# WaterCirculation.net
KiCad netlist of a schematic drawn in EAGLE
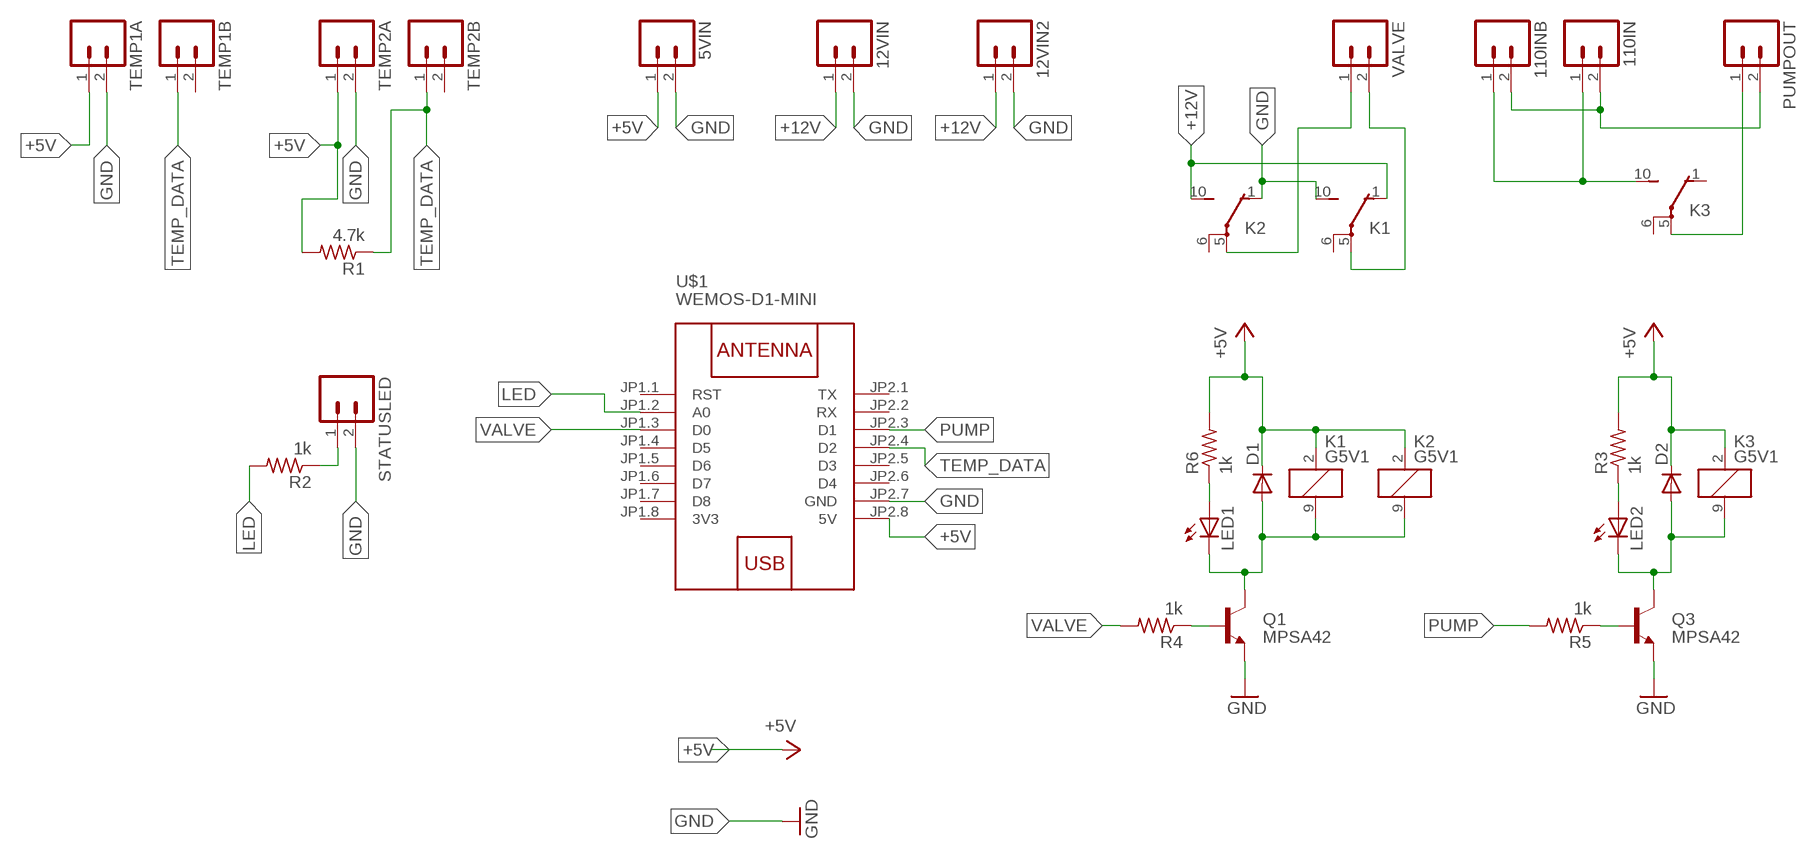
[diagram p0: schematic, sheet 1]

(export (version "E")
  (design (tool "Eeschema 10.0.6"))
  (components
    (comp (ref "5VIN")
      (value "M023.5MM")
      (footprint "eagle-import:SCREWTERMINAL-3.5MM-2")
      (libsource (lib "eagle-import") (part "M023.5MM"))
    )
    (comp (ref "12VIN")
      (value "M023.5MM")
      (footprint "eagle-import:SCREWTERMINAL-3.5MM-2")
      (libsource (lib "eagle-import") (part "M023.5MM"))
    )
    (comp (ref "12VIN2")
      (value "M023.5MM")
      (footprint "eagle-import:SCREWTERMINAL-3.5MM-2")
      (libsource (lib "eagle-import") (part "M023.5MM"))
    )
    (comp (ref "110IN")
      (value "M023.5MM")
      (footprint "eagle-import:SCREWTERMINAL-3.5MM-2")
      (libsource (lib "eagle-import") (part "M023.5MM"))
    )
    (comp (ref "110INB")
      (value "M023.5MM")
      (footprint "eagle-import:SCREWTERMINAL-3.5MM-2")
      (libsource (lib "eagle-import") (part "M023.5MM"))
    )
    (comp (ref "D1")
      (value "DIODE-SOD123")
      (footprint "eagle-import:SOD123")
      (libsource (lib "eagle-import") (part "DIODE-SOD123"))
    )
    (comp (ref "D2")
      (value "DIODE-SOD123")
      (footprint "eagle-import:SOD123")
      (libsource (lib "eagle-import") (part "DIODE-SOD123"))
    )
    (comp (ref "K1")
      (value "G5V1")
      (footprint "eagle-import:G5V1")
      (libsource (lib "eagle-import") (part "G5V1"))
    )
    (comp (ref "K2")
      (value "G5V1")
      (footprint "eagle-import:G5V1")
      (libsource (lib "eagle-import") (part "G5V1"))
    )
    (comp (ref "K3")
      (value "G5V1")
      (footprint "eagle-import:G5V1")
      (libsource (lib "eagle-import") (part "G5V1"))
    )
    (comp (ref "LED1")
      (value "LEDCHIP-LED0805")
      (footprint "eagle-import:CHIP-LED0805")
      (libsource (lib "eagle-import") (part "LEDCHIP-LED0805"))
    )
    (comp (ref "LED2")
      (value "LEDCHIP-LED0805")
      (footprint "eagle-import:CHIP-LED0805")
      (libsource (lib "eagle-import") (part "LEDCHIP-LED0805"))
    )
    (comp (ref "PUMPOUT")
      (value "M023.5MM")
      (footprint "eagle-import:SCREWTERMINAL-3.5MM-2")
      (libsource (lib "eagle-import") (part "M023.5MM"))
    )
    (comp (ref "Q1")
      (value "MPSA42")
      (footprint "eagle-import:SOT23-3")
      (libsource (lib "eagle-import") (part "TRANSISTOR_NPNMPSA42"))
    )
    (comp (ref "Q3")
      (value "MPSA42")
      (footprint "eagle-import:SOT23-3")
      (libsource (lib "eagle-import") (part "TRANSISTOR_NPNMPSA42"))
    )
    (comp (ref "R1")
      (value "4.7k")
      (footprint "eagle-import:R0805")
      (libsource (lib "eagle-import") (part "R-US_R0805"))
    )
    (comp (ref "R2")
      (value "1k")
      (footprint "eagle-import:R0805")
      (libsource (lib "eagle-import") (part "R-US_R0805"))
    )
    (comp (ref "R3")
      (value "1k")
      (footprint "eagle-import:R0805")
      (libsource (lib "eagle-import") (part "R-US_R0805"))
    )
    (comp (ref "R4")
      (value "1k")
      (footprint "eagle-import:R0805")
      (libsource (lib "eagle-import") (part "R-US_R0805"))
    )
    (comp (ref "R5")
      (value "1k")
      (footprint "eagle-import:R0805")
      (libsource (lib "eagle-import") (part "R-US_R0805"))
    )
    (comp (ref "R6")
      (value "1k")
      (footprint "eagle-import:R0805")
      (libsource (lib "eagle-import") (part "R-US_R0805"))
    )
    (comp (ref "STATUSLED")
      (value "M023.5MM")
      (footprint "eagle-import:SCREWTERMINAL-3.5MM-2")
      (libsource (lib "eagle-import") (part "M023.5MM"))
    )
    (comp (ref "TEMP1A")
      (value "M023.5MM")
      (footprint "eagle-import:SCREWTERMINAL-3.5MM-2")
      (libsource (lib "eagle-import") (part "M023.5MM"))
    )
    (comp (ref "TEMP1B")
      (value "M023.5MM")
      (footprint "eagle-import:SCREWTERMINAL-3.5MM-2")
      (libsource (lib "eagle-import") (part "M023.5MM"))
    )
    (comp (ref "TEMP2A")
      (value "M023.5MM")
      (footprint "eagle-import:SCREWTERMINAL-3.5MM-2")
      (libsource (lib "eagle-import") (part "M023.5MM"))
    )
    (comp (ref "TEMP2B")
      (value "M023.5MM")
      (footprint "eagle-import:SCREWTERMINAL-3.5MM-2")
      (libsource (lib "eagle-import") (part "M023.5MM"))
    )
    (comp (ref "U$1")
      (value "WEMOS-D1-MINI")
      (footprint "eagle-import:WEMOS-D1-MINI")
      (libsource (lib "eagle-import") (part "WEMOS-D1-MINI"))
    )
    (comp (ref "VALVE")
      (value "M023.5MM")
      (footprint "eagle-import:SCREWTERMINAL-3.5MM-2")
      (libsource (lib "eagle-import") (part "M023.5MM"))
    )
  )
  (nets
    (net (code "1") (name "+5V") (class "Default")
      (node (ref "5VIN") (pin "1") (pinfunction "1_1") (pintype "passive"))
      (node (ref "D1") (pin "C") (pinfunction "C_C") (pintype "passive"))
      (node (ref "D2") (pin "C") (pinfunction "C_C") (pintype "passive"))
      (node (ref "K1") (pin "2") (pinfunction "1_2") (pintype "passive"))
      (node (ref "K2") (pin "2") (pinfunction "1_2") (pintype "passive"))
      (node (ref "K3") (pin "2") (pinfunction "1_2") (pintype "passive"))
      (node (ref "R1") (pin "2") (pinfunction "2_2") (pintype "passive"))
      (node (ref "R3") (pin "2") (pinfunction "2_2") (pintype "passive"))
      (node (ref "R6") (pin "2") (pinfunction "2_2") (pintype "passive"))
      (node (ref "TEMP1A") (pin "1") (pinfunction "1_1") (pintype "passive"))
      (node (ref "TEMP2A") (pin "1") (pinfunction "1_1") (pintype "passive"))
      (node (ref "U$1") (pin "JP2.8") (pinfunction "5V_JP2.8") (pintype "power_in"))
    )
    (net (code "2") (name "+12V") (class "Default")
      (node (ref "12VIN") (pin "1") (pinfunction "1_1") (pintype "passive"))
      (node (ref "12VIN2") (pin "1") (pinfunction "1_1") (pintype "passive"))
      (node (ref "K1") (pin "1") (pinfunction "O_1") (pintype "passive"))
      (node (ref "K2") (pin "10") (pinfunction "S_10") (pintype "passive"))
    )
    (net (code "3") (name "/3V3") (class "Default")
      (node (ref "U$1") (pin "JP1.8") (pinfunction "3V3_JP1.8") (pintype "power_in"))
    )
    (net (code "4") (name "GND") (class "Default")
      (node (ref "12VIN") (pin "2") (pinfunction "2_2") (pintype "passive"))
      (node (ref "12VIN2") (pin "2") (pinfunction "2_2") (pintype "passive"))
      (node (ref "5VIN") (pin "2") (pinfunction "2_2") (pintype "passive"))
      (node (ref "K1") (pin "10") (pinfunction "S_10") (pintype "passive"))
      (node (ref "K2") (pin "1") (pinfunction "O_1") (pintype "passive"))
      (node (ref "Q1") (pin "2") (pinfunction "E_2") (pintype "passive"))
      (node (ref "Q3") (pin "2") (pinfunction "E_2") (pintype "passive"))
      (node (ref "STATUSLED") (pin "2") (pinfunction "2_2") (pintype "passive"))
      (node (ref "TEMP1A") (pin "2") (pinfunction "2_2") (pintype "passive"))
      (node (ref "TEMP2A") (pin "2") (pinfunction "2_2") (pintype "passive"))
      (node (ref "U$1") (pin "JP2.7") (pinfunction "GND_JP2.7") (pintype "power_in"))
    )
    (net (code "5") (name "LED") (class "Default")
      (node (ref "R2") (pin "2") (pinfunction "2_2") (pintype "passive"))
      (node (ref "U$1") (pin "JP1.2") (pinfunction "A0_JP1.2") (pintype "bidirectional"))
    )
    (net (code "6") (name "Net-(110IN-Pad2)") (class "Default")
      (node (ref "110IN") (pin "2") (pinfunction "2_2") (pintype "passive"))
      (node (ref "110INB") (pin "2") (pinfunction "2_2") (pintype "passive"))
      (node (ref "PUMPOUT") (pin "2") (pinfunction "2_2") (pintype "passive"))
    )
    (net (code "7") (name "Net-(K1A-2)") (class "Default")
      (node (ref "D1") (pin "A") (pinfunction "A_A") (pintype "passive"))
      (node (ref "K1") (pin "9") (pinfunction "2_9") (pintype "passive"))
      (node (ref "K2") (pin "9") (pinfunction "2_9") (pintype "passive"))
      (node (ref "LED1") (pin "C") (pinfunction "C_C") (pintype "passive"))
      (node (ref "Q1") (pin "3") (pinfunction "C_3") (pintype "passive"))
    )
    (net (code "8") (name "Net-(K1B-P-Pad5)") (class "Default")
      (node (ref "K1") (pin "5") (pinfunction "P_5") (pintype "passive"))
      (node (ref "VALVE") (pin "2") (pinfunction "2_2") (pintype "passive"))
    )
    (net (code "9") (name "Net-(K2B-P-Pad5)") (class "Default")
      (node (ref "K2") (pin "5") (pinfunction "P_5") (pintype "passive"))
      (node (ref "VALVE") (pin "1") (pinfunction "1_1") (pintype "passive"))
    )
    (net (code "10") (name "Net-(K3A-2)") (class "Default")
      (node (ref "D2") (pin "A") (pinfunction "A_A") (pintype "passive"))
      (node (ref "K3") (pin "9") (pinfunction "2_9") (pintype "passive"))
      (node (ref "LED2") (pin "C") (pinfunction "C_C") (pintype "passive"))
      (node (ref "Q3") (pin "3") (pinfunction "C_3") (pintype "passive"))
    )
    (net (code "11") (name "Net-(K3B-P-Pad5)") (class "Default")
      (node (ref "K3") (pin "5") (pinfunction "P_5") (pintype "passive"))
      (node (ref "PUMPOUT") (pin "1") (pinfunction "1_1") (pintype "passive"))
    )
    (net (code "12") (name "Net-(K3B-S)") (class "Default")
      (node (ref "110IN") (pin "1") (pinfunction "1_1") (pintype "passive"))
      (node (ref "110INB") (pin "1") (pinfunction "1_1") (pintype "passive"))
      (node (ref "K3") (pin "10") (pinfunction "S_10") (pintype "passive"))
    )
    (net (code "13") (name "Net-(LED1-PadA)") (class "Default")
      (node (ref "LED1") (pin "A") (pinfunction "A_A") (pintype "passive"))
      (node (ref "R6") (pin "1") (pinfunction "1_1") (pintype "passive"))
    )
    (net (code "14") (name "Net-(LED2-PadA)") (class "Default")
      (node (ref "LED2") (pin "A") (pinfunction "A_A") (pintype "passive"))
      (node (ref "R3") (pin "1") (pinfunction "1_1") (pintype "passive"))
    )
    (net (code "15") (name "Net-(Q1-B)") (class "Default")
      (node (ref "Q1") (pin "1") (pinfunction "B_1") (pintype "passive"))
      (node (ref "R4") (pin "1") (pinfunction "1_1") (pintype "passive"))
    )
    (net (code "16") (name "Net-(Q3-B)") (class "Default")
      (node (ref "Q3") (pin "1") (pinfunction "B_1") (pintype "passive"))
      (node (ref "R5") (pin "1") (pinfunction "1_1") (pintype "passive"))
    )
    (net (code "17") (name "Net-(R2-Pad1)") (class "Default")
      (node (ref "R2") (pin "1") (pinfunction "1_1") (pintype "passive"))
      (node (ref "STATUSLED") (pin "1") (pinfunction "1_1") (pintype "passive"))
    )
    (net (code "18") (name "PUMP") (class "Default")
      (node (ref "R5") (pin "2") (pinfunction "2_2") (pintype "passive"))
      (node (ref "U$1") (pin "JP2.3") (pinfunction "D1_JP2.3") (pintype "bidirectional"))
    )
    (net (code "19") (name "TEMP_DATA") (class "Default")
      (node (ref "R1") (pin "1") (pinfunction "1_1") (pintype "passive"))
      (node (ref "TEMP1B") (pin "1") (pinfunction "1_1") (pintype "passive"))
      (node (ref "TEMP2B") (pin "1") (pinfunction "1_1") (pintype "passive"))
      (node (ref "U$1") (pin "JP2.4") (pinfunction "D2_JP2.4") (pintype "bidirectional"))
    )
    (net (code "20") (name "VALVE") (class "Default")
      (node (ref "R4") (pin "2") (pinfunction "2_2") (pintype "passive"))
      (node (ref "U$1") (pin "JP1.3") (pinfunction "D0_JP1.3") (pintype "bidirectional"))
    )
    (net (code "21") (name "unconnected-(K1B-P-Pad6)") (class "Default")
      (node (ref "K1") (pin "6") (pinfunction "P_6") (pintype "passive"))
    )
    (net (code "22") (name "unconnected-(K2B-P-Pad6)") (class "Default")
      (node (ref "K2") (pin "6") (pinfunction "P_6") (pintype "passive"))
    )
    (net (code "23") (name "unconnected-(K3B-O-Pad1)") (class "Default")
      (node (ref "K3") (pin "1") (pinfunction "O_1") (pintype "passive"))
    )
    (net (code "24") (name "unconnected-(K3B-P-Pad6)") (class "Default")
      (node (ref "K3") (pin "6") (pinfunction "P_6") (pintype "passive"))
    )
    (net (code "25") (name "unconnected-(TEMP1B-Pad2)") (class "Default")
      (node (ref "TEMP1B") (pin "2") (pinfunction "2_2") (pintype "passive"))
    )
    (net (code "26") (name "unconnected-(TEMP2B-Pad2)") (class "Default")
      (node (ref "TEMP2B") (pin "2") (pinfunction "2_2") (pintype "passive"))
    )
    (net (code "27") (name "unconnected-(U$1-D3-PadJP2.5)") (class "Default")
      (node (ref "U$1") (pin "JP2.5") (pinfunction "D3_JP2.5") (pintype "bidirectional"))
    )
    (net (code "28") (name "unconnected-(U$1-D4-PadJP2.6)") (class "Default")
      (node (ref "U$1") (pin "JP2.6") (pinfunction "D4_JP2.6") (pintype "bidirectional"))
    )
    (net (code "29") (name "unconnected-(U$1-D5-PadJP1.4)") (class "Default")
      (node (ref "U$1") (pin "JP1.4") (pinfunction "D5_JP1.4") (pintype "bidirectional"))
    )
    (net (code "30") (name "unconnected-(U$1-D6-PadJP1.5)") (class "Default")
      (node (ref "U$1") (pin "JP1.5") (pinfunction "D6_JP1.5") (pintype "bidirectional"))
    )
    (net (code "31") (name "unconnected-(U$1-D7-PadJP1.6)") (class "Default")
      (node (ref "U$1") (pin "JP1.6") (pinfunction "D7_JP1.6") (pintype "bidirectional"))
    )
    (net (code "32") (name "unconnected-(U$1-D8-PadJP1.7)") (class "Default")
      (node (ref "U$1") (pin "JP1.7") (pinfunction "D8_JP1.7") (pintype "bidirectional"))
    )
    (net (code "33") (name "unconnected-(U$1-RST-PadJP1.1)") (class "Default")
      (node (ref "U$1") (pin "JP1.1") (pinfunction "RST_JP1.1") (pintype "bidirectional"))
    )
    (net (code "34") (name "unconnected-(U$1-RX-PadJP2.2)") (class "Default")
      (node (ref "U$1") (pin "JP2.2") (pinfunction "RX_JP2.2") (pintype "bidirectional"))
    )
    (net (code "35") (name "unconnected-(U$1-TX-PadJP2.1)") (class "Default")
      (node (ref "U$1") (pin "JP2.1") (pinfunction "TX_JP2.1") (pintype "bidirectional"))
    )
  )
)
